# Sheet1.net
KiCad netlist of a schematic drawn in Altium Designer
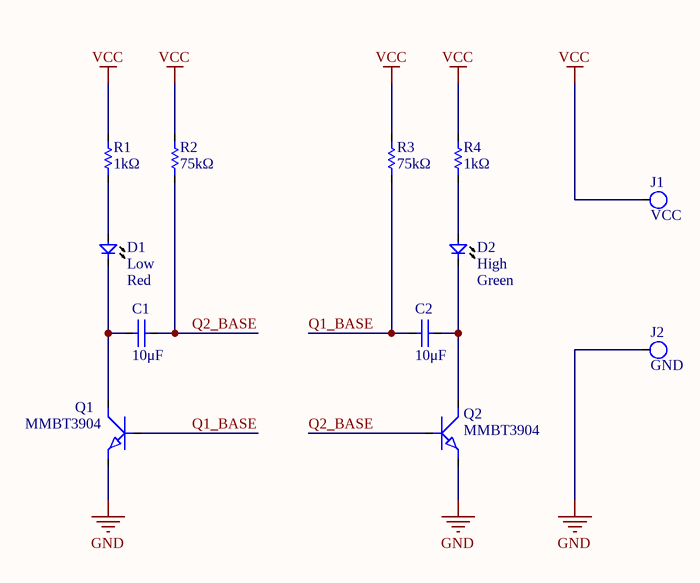
[diagram p0: Sheet1.SchDoc]

(export (version "E")
  (design (tool "Eeschema 10.0.6"))
  (components
    (comp (ref "C1")
      (value "10μF")
      (footprint "0805_CAP")
      (description "Generic non-polarised capacitor.")
      (libsource (lib "Altium_Workshop_2020") (part "C"))
    )
    (comp (ref "C2")
      (value "10μF")
      (footprint "0805_CAP")
      (description "Generic non-polarised capacitor.")
      (libsource (lib "Altium_Workshop_2020") (part "C"))
    )
    (comp (ref "D1")
      (value "Low")
      (footprint "0805_DIODE")
      (description "Generic LED.")
      (fields (field (name "COLOR") "Red"))
      (libsource (lib "Altium_Workshop_2020") (part "LED"))
    )
    (comp (ref "D2")
      (value "High")
      (footprint "0805_DIODE")
      (description "Generic LED.")
      (fields (field (name "COLOR") "Green"))
      (libsource (lib "Altium_Workshop_2020") (part "LED"))
    )
    (comp (ref "J1")
      (value "VCC")
      (footprint "PIN_1MM")
      (description "Generic wire-to-board point or test point.")
      (libsource (lib "Altium_Workshop_2020") (part "TEST_POINT"))
    )
    (comp (ref "J2")
      (value "GND")
      (footprint "PIN_1MM")
      (description "Generic wire-to-board point or test point.")
      (libsource (lib "Altium_Workshop_2020") (part "TEST_POINT"))
    )
    (comp (ref "Q1")
      (value "MMBT3904")
      (footprint "SOT23-3")
      (description "Generic NPN bipolar transistor.")
      (libsource (lib "Altium_Workshop_2020") (part "NPN_BJT"))
    )
    (comp (ref "Q2")
      (value "MMBT3904")
      (footprint "SOT23-3")
      (description "Generic NPN bipolar transistor.")
      (libsource (lib "") (part "NPN_BJT_1"))
    )
    (comp (ref "R1")
      (value "1kΩ")
      (footprint "0805_RES")
      (description "Generic resistor.")
      (libsource (lib "Altium_Workshop_2020") (part "R"))
    )
    (comp (ref "R2")
      (value "75kΩ")
      (footprint "0805_RES")
      (description "Generic resistor.")
      (libsource (lib "Altium_Workshop_2020") (part "R"))
    )
    (comp (ref "R3")
      (value "75kΩ")
      (footprint "0805_RES")
      (description "Generic resistor.")
      (libsource (lib "Altium_Workshop_2020") (part "R"))
    )
    (comp (ref "R4")
      (value "1kΩ")
      (footprint "0805_RES")
      (description "Generic resistor.")
      (libsource (lib "Altium_Workshop_2020") (part "R"))
    )
  )
  (nets
    (net (code "1") (name "/Q1_BASE") (class "Default")
      (node (ref "C2") (pin "2") (pinfunction "2_2") (pintype "passive"))
      (node (ref "Q1") (pin "1") (pinfunction "B_1") (pintype "passive"))
      (node (ref "R3") (pin "1") (pintype "passive"))
    )
    (net (code "2") (name "/Q2_BASE") (class "Default")
      (node (ref "C1") (pin "1") (pinfunction "1_1") (pintype "passive"))
      (node (ref "Q2") (pin "1") (pinfunction "B_1") (pintype "passive"))
      (node (ref "R2") (pin "1") (pintype "passive"))
    )
    (net (code "3") (name "GND") (class "Default")
      (node (ref "J2") (pin "1") (pinfunction "J_1") (pintype "passive"))
      (node (ref "Q1") (pin "2") (pinfunction "E_2") (pintype "passive"))
      (node (ref "Q2") (pin "2") (pinfunction "E_2") (pintype "passive"))
    )
    (net (code "4") (name "Net-(D1-PadA)") (class "Default")
      (node (ref "D1") (pin "A") (pinfunction "A_A") (pintype "passive"))
      (node (ref "R1") (pin "1") (pintype "passive"))
    )
    (net (code "5") (name "Net-(D2-PadA)") (class "Default")
      (node (ref "D2") (pin "A") (pinfunction "A_A") (pintype "passive"))
      (node (ref "R4") (pin "1") (pintype "passive"))
    )
    (net (code "6") (name "Net-(Q1-C)") (class "Default")
      (node (ref "C1") (pin "2") (pinfunction "2_2") (pintype "passive"))
      (node (ref "D1") (pin "K") (pinfunction "K_K") (pintype "passive"))
      (node (ref "Q1") (pin "3") (pinfunction "C_3") (pintype "passive"))
    )
    (net (code "7") (name "Net-(Q2-C)") (class "Default")
      (node (ref "C2") (pin "1") (pinfunction "1_1") (pintype "passive"))
      (node (ref "D2") (pin "K") (pinfunction "K_K") (pintype "passive"))
      (node (ref "Q2") (pin "3") (pinfunction "C_3") (pintype "passive"))
    )
    (net (code "8") (name "VCC") (class "Default")
      (node (ref "J1") (pin "1") (pinfunction "J_1") (pintype "passive"))
      (node (ref "R1") (pin "2") (pintype "passive"))
      (node (ref "R2") (pin "2") (pintype "passive"))
      (node (ref "R3") (pin "2") (pintype "passive"))
      (node (ref "R4") (pin "2") (pintype "passive"))
    )
  )
)
